# MainBoard.net
KiCad netlist of a schematic drawn in EAGLE
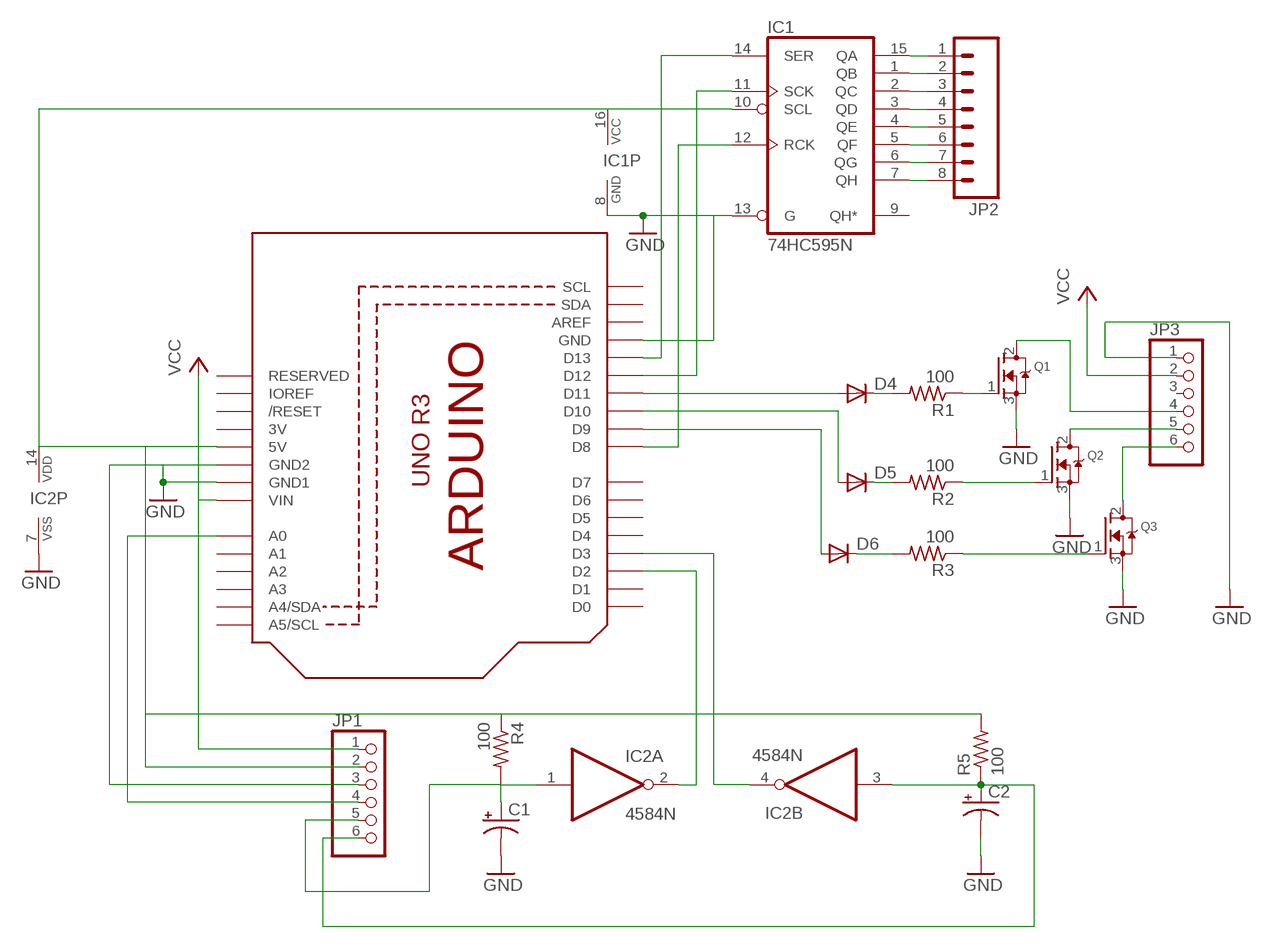
[diagram p0: schematic, sheet 1]

(export (version "E")
  (design (tool "Eeschema 10.0.6"))
  (components
    (comp (ref "C1")
      (value "CPOL-USE2.5-5")
      (footprint "eagle-import:E2,5-5")
      (libsource (lib "eagle-import") (part "CPOL-USE2.5-5"))
    )
    (comp (ref "C2")
      (value "CPOL-USE2.5-5")
      (footprint "eagle-import:E2,5-5")
      (libsource (lib "eagle-import") (part "CPOL-USE2.5-5"))
    )
    (comp (ref "D4")
      (value "1N4148DO35-7")
      (footprint "eagle-import:DO35-7")
      (libsource (lib "eagle-import") (part "1N4148DO35-7"))
    )
    (comp (ref "D5")
      (value "1N4148DO35-7")
      (footprint "eagle-import:DO35-7")
      (libsource (lib "eagle-import") (part "1N4148DO35-7"))
    )
    (comp (ref "D6")
      (value "1N4148DO35-7")
      (footprint "eagle-import:DO35-7")
      (libsource (lib "eagle-import") (part "1N4148DO35-7"))
    )
    (comp (ref "IC1")
      (value "74HC595N")
      (footprint "eagle-import:DIL16")
      (libsource (lib "eagle-import") (part "74595NHC"))
    )
    (comp (ref "IC2")
      (value "4584N")
      (footprint "eagle-import:DIL14")
      (libsource (lib "eagle-import") (part "4584N"))
    )
    (comp (ref "JP1")
      (value "PINHD-1X6LOCK")
      (footprint "eagle-import:1X06-BIGLOCK")
      (libsource (lib "eagle-import") (part "PINHD-1X6LOCK"))
    )
    (comp (ref "JP2")
      (value "M08LOCK")
      (footprint "eagle-import:1X08_LOCK")
      (libsource (lib "eagle-import") (part "M08LOCK"))
    )
    (comp (ref "JP3")
      (value "PINHD-1X6LOCK")
      (footprint "eagle-import:1X06-BIGLOCK")
      (libsource (lib "eagle-import") (part "PINHD-1X6LOCK"))
    )
    (comp (ref "Q1")
      (value "MOSFET-NGDS_TO220V")
      (footprint "eagle-import:TO220V")
      (libsource (lib "eagle-import") (part "MOSFET-NGDS_TO220V"))
    )
    (comp (ref "Q2")
      (value "MOSFET-NGDS_TO220V")
      (footprint "eagle-import:TO220V")
      (libsource (lib "eagle-import") (part "MOSFET-NGDS_TO220V"))
    )
    (comp (ref "Q3")
      (value "MOSFET-NGDS_TO220V")
      (footprint "eagle-import:TO220V")
      (libsource (lib "eagle-import") (part "MOSFET-NGDS_TO220V"))
    )
    (comp (ref "R1")
      (value "100")
      (footprint "eagle-import:0207_10")
      (libsource (lib "eagle-import") (part "R-US_0207/10"))
    )
    (comp (ref "R2")
      (value "100")
      (footprint "eagle-import:0207_10")
      (libsource (lib "eagle-import") (part "R-US_0207/10"))
    )
    (comp (ref "R3")
      (value "100")
      (footprint "eagle-import:0207_10")
      (libsource (lib "eagle-import") (part "R-US_0207/10"))
    )
    (comp (ref "R4")
      (value "100")
      (footprint "eagle-import:0207_10")
      (libsource (lib "eagle-import") (part "R-US_0207/10"))
    )
    (comp (ref "R5")
      (value "100")
      (footprint "eagle-import:0207_10")
      (libsource (lib "eagle-import") (part "R-US_0207/10"))
    )
    (comp (ref "U1")
      (value "ARDUINOR3-BPLACE")
      (footprint "eagle-import:ARDUINOR3-BPLACE")
      (libsource (lib "eagle-import") (part "ARDUINOR3-BPLACE"))
    )
  )
  (nets
    (net (code "1") (name "/3V") (class "Default")
      (node (ref "U1") (pin "3V") (pinfunction "3V_3V") (pintype "power_in"))
    )
    (net (code "2") (name "GND") (class "Default")
      (node (ref "C1") (pin "-") (pinfunction "-_-") (pintype "passive"))
      (node (ref "C2") (pin "-") (pinfunction "-_-") (pintype "passive"))
      (node (ref "IC1") (pin "13") (pinfunction "G_13") (pintype "input"))
      (node (ref "IC1") (pin "8") (pinfunction "GND_8") (pintype "power_in"))
      (node (ref "IC2") (pin "7") (pinfunction "VSS_7") (pintype "power_in"))
      (node (ref "JP1") (pin "3") (pinfunction "3_3") (pintype "passive"))
      (node (ref "JP3") (pin "1") (pinfunction "1_1") (pintype "passive"))
      (node (ref "Q1") (pin "3") (pinfunction "S_3") (pintype "bidirectional"))
      (node (ref "Q2") (pin "3") (pinfunction "S_3") (pintype "bidirectional"))
      (node (ref "Q3") (pin "3") (pinfunction "S_3") (pintype "bidirectional"))
      (node (ref "U1") (pin "GND") (pinfunction "GND_GND") (pintype "power_in"))
      (node (ref "U1") (pin "GND1") (pinfunction "GND1_GND1") (pintype "power_in"))
      (node (ref "U1") (pin "GND2") (pinfunction "GND2_GND2") (pintype "power_in"))
    )
    (net (code "3") (name "Net-(D4-PadA)") (class "Default")
      (node (ref "D4") (pin "A") (pinfunction "A_A") (pintype "passive"))
      (node (ref "U1") (pin "D11") (pinfunction "D11_D11") (pintype "bidirectional"))
    )
    (net (code "4") (name "Net-(D4-PadC)") (class "Default")
      (node (ref "D4") (pin "C") (pinfunction "C_C") (pintype "passive"))
      (node (ref "R1") (pin "2") (pinfunction "2_2") (pintype "passive"))
    )
    (net (code "5") (name "Net-(D5-PadA)") (class "Default")
      (node (ref "D5") (pin "A") (pinfunction "A_A") (pintype "passive"))
      (node (ref "U1") (pin "D10") (pinfunction "D10_D10") (pintype "bidirectional"))
    )
    (net (code "6") (name "Net-(D5-PadC)") (class "Default")
      (node (ref "D5") (pin "C") (pinfunction "C_C") (pintype "passive"))
      (node (ref "R2") (pin "2") (pinfunction "2_2") (pintype "passive"))
    )
    (net (code "7") (name "Net-(D6-PadA)") (class "Default")
      (node (ref "D6") (pin "A") (pinfunction "A_A") (pintype "passive"))
      (node (ref "U1") (pin "D9") (pinfunction "D9_D9") (pintype "bidirectional"))
    )
    (net (code "8") (name "Net-(D6-PadC)") (class "Default")
      (node (ref "D6") (pin "C") (pinfunction "C_C") (pintype "passive"))
      (node (ref "R3") (pin "2") (pinfunction "2_2") (pintype "passive"))
    )
    (net (code "9") (name "Net-(IC1A-QA)") (class "Default")
      (node (ref "IC1") (pin "15") (pinfunction "QA_15") (pintype "tri_state"))
      (node (ref "JP2") (pin "1") (pinfunction "1_1") (pintype "passive"))
    )
    (net (code "10") (name "Net-(IC1A-QB)") (class "Default")
      (node (ref "IC1") (pin "1") (pinfunction "QB_1") (pintype "tri_state"))
      (node (ref "JP2") (pin "2") (pinfunction "2_2") (pintype "passive"))
    )
    (net (code "11") (name "Net-(IC1A-QC)") (class "Default")
      (node (ref "IC1") (pin "2") (pinfunction "QC_2") (pintype "tri_state"))
      (node (ref "JP2") (pin "3") (pinfunction "3_3") (pintype "passive"))
    )
    (net (code "12") (name "Net-(IC1A-QD)") (class "Default")
      (node (ref "IC1") (pin "3") (pinfunction "QD_3") (pintype "tri_state"))
      (node (ref "JP2") (pin "4") (pinfunction "4_4") (pintype "passive"))
    )
    (net (code "13") (name "Net-(IC1A-QE)") (class "Default")
      (node (ref "IC1") (pin "4") (pinfunction "QE_4") (pintype "tri_state"))
      (node (ref "JP2") (pin "5") (pinfunction "5_5") (pintype "passive"))
    )
    (net (code "14") (name "Net-(IC1A-QF)") (class "Default")
      (node (ref "IC1") (pin "5") (pinfunction "QF_5") (pintype "tri_state"))
      (node (ref "JP2") (pin "6") (pinfunction "6_6") (pintype "passive"))
    )
    (net (code "15") (name "Net-(IC1A-QG)") (class "Default")
      (node (ref "IC1") (pin "6") (pinfunction "QG_6") (pintype "tri_state"))
      (node (ref "JP2") (pin "7") (pinfunction "7_7") (pintype "passive"))
    )
    (net (code "16") (name "Net-(IC1A-QH)") (class "Default")
      (node (ref "IC1") (pin "7") (pinfunction "QH_7") (pintype "tri_state"))
      (node (ref "JP2") (pin "8") (pinfunction "8_8") (pintype "passive"))
    )
    (net (code "17") (name "Net-(IC1A-RCK)") (class "Default")
      (node (ref "IC1") (pin "12") (pinfunction "RCK_12") (pintype "input"))
      (node (ref "U1") (pin "D8") (pinfunction "D8_D8") (pintype "bidirectional"))
    )
    (net (code "18") (name "Net-(IC1A-SCK)") (class "Default")
      (node (ref "IC1") (pin "11") (pinfunction "SCK_11") (pintype "input"))
      (node (ref "U1") (pin "D12") (pinfunction "D12_D12") (pintype "bidirectional"))
    )
    (net (code "19") (name "Net-(IC1A-SCL)") (class "Default")
      (node (ref "IC1") (pin "10") (pinfunction "SCL_10") (pintype "input"))
      (node (ref "IC1") (pin "16") (pinfunction "VCC_16") (pintype "power_in"))
      (node (ref "IC2") (pin "14") (pinfunction "VDD_14") (pintype "power_in"))
      (node (ref "JP1") (pin "2") (pinfunction "2_2") (pintype "passive"))
      (node (ref "R4") (pin "1") (pinfunction "1_1") (pintype "passive"))
      (node (ref "R5") (pin "2") (pinfunction "2_2") (pintype "passive"))
      (node (ref "U1") (pin "5V") (pinfunction "5V_5V") (pintype "power_in"))
    )
    (net (code "20") (name "Net-(IC1A-SER)") (class "Default")
      (node (ref "IC1") (pin "14") (pinfunction "SER_14") (pintype "input"))
      (node (ref "U1") (pin "D13") (pinfunction "D13_D13") (pintype "bidirectional"))
    )
    (net (code "21") (name "Net-(IC2A-I)") (class "Default")
      (node (ref "C1") (pin "+") (pinfunction "+_+") (pintype "passive"))
      (node (ref "IC2") (pin "1") (pinfunction "I_1") (pintype "input"))
      (node (ref "JP1") (pin "5") (pinfunction "5_5") (pintype "passive"))
      (node (ref "R4") (pin "2") (pinfunction "2_2") (pintype "passive"))
    )
    (net (code "22") (name "Net-(IC2A-O)") (class "Default")
      (node (ref "IC2") (pin "2") (pinfunction "O_2") (pintype "output"))
      (node (ref "U1") (pin "D2") (pinfunction "D2_D2") (pintype "bidirectional"))
    )
    (net (code "23") (name "Net-(IC2B-I)") (class "Default")
      (node (ref "C2") (pin "+") (pinfunction "+_+") (pintype "passive"))
      (node (ref "IC2") (pin "3") (pinfunction "I_3") (pintype "input"))
      (node (ref "JP1") (pin "6") (pinfunction "6_6") (pintype "passive"))
      (node (ref "R5") (pin "1") (pinfunction "1_1") (pintype "passive"))
    )
    (net (code "24") (name "Net-(IC2B-O)") (class "Default")
      (node (ref "IC2") (pin "4") (pinfunction "O_4") (pintype "output"))
      (node (ref "U1") (pin "D3") (pinfunction "D3_D3") (pintype "bidirectional"))
    )
    (net (code "25") (name "Net-(JP1-Pad4)") (class "Default")
      (node (ref "JP1") (pin "4") (pinfunction "4_4") (pintype "passive"))
      (node (ref "U1") (pin "A0") (pinfunction "A0_A0") (pintype "bidirectional"))
    )
    (net (code "26") (name "Net-(Q1-D)") (class "Default")
      (node (ref "JP3") (pin "4") (pinfunction "4_4") (pintype "passive"))
      (node (ref "Q1") (pin "2") (pinfunction "D_2") (pintype "bidirectional"))
    )
    (net (code "27") (name "Net-(Q1-G)") (class "Default")
      (node (ref "Q1") (pin "1") (pinfunction "G_1") (pintype "bidirectional"))
      (node (ref "R1") (pin "1") (pinfunction "1_1") (pintype "passive"))
    )
    (net (code "28") (name "Net-(Q2-D)") (class "Default")
      (node (ref "JP3") (pin "5") (pinfunction "5_5") (pintype "passive"))
      (node (ref "Q2") (pin "2") (pinfunction "D_2") (pintype "bidirectional"))
    )
    (net (code "29") (name "Net-(Q2-G)") (class "Default")
      (node (ref "Q2") (pin "1") (pinfunction "G_1") (pintype "bidirectional"))
      (node (ref "R2") (pin "1") (pinfunction "1_1") (pintype "passive"))
    )
    (net (code "30") (name "Net-(Q3-D)") (class "Default")
      (node (ref "JP3") (pin "6") (pinfunction "6_6") (pintype "passive"))
      (node (ref "Q3") (pin "2") (pinfunction "D_2") (pintype "bidirectional"))
    )
    (net (code "31") (name "Net-(Q3-G)") (class "Default")
      (node (ref "Q3") (pin "1") (pinfunction "G_1") (pintype "bidirectional"))
      (node (ref "R3") (pin "1") (pinfunction "1_1") (pintype "passive"))
    )
    (net (code "32") (name "VCC") (class "Default")
      (node (ref "JP1") (pin "1") (pinfunction "1_1") (pintype "passive"))
      (node (ref "JP3") (pin "2") (pinfunction "2_2") (pintype "passive"))
      (node (ref "U1") (pin "VIN") (pinfunction "VIN_VIN") (pintype "power_in"))
    )
    (net (code "33") (name "unconnected-(IC1A-QH*-Pad9)") (class "Default")
      (node (ref "IC1") (pin "9") (pinfunction "QH*_9") (pintype "tri_state"))
    )
    (net (code "34") (name "unconnected-(JP3-Pad3)") (class "Default")
      (node (ref "JP3") (pin "3") (pinfunction "3_3") (pintype "passive"))
    )
    (net (code "35") (name "unconnected-(U1-A4{slash}SDA-PadA4)") (class "Default")
      (node (ref "U1") (pin "A4") (pinfunction "A4/SDA_A4") (pintype "bidirectional"))
    )
    (net (code "36") (name "unconnected-(U1-A5{slash}SCL-PadA5)") (class "Default")
      (node (ref "U1") (pin "A5") (pinfunction "A5/SCL_A5") (pintype "bidirectional"))
    )
    (net (code "37") (name "unconnected-(U1-PadA1)") (class "Default")
      (node (ref "U1") (pin "A1") (pinfunction "A1_A1") (pintype "bidirectional"))
    )
    (net (code "38") (name "unconnected-(U1-PadA2)") (class "Default")
      (node (ref "U1") (pin "A2") (pinfunction "A2_A2") (pintype "bidirectional"))
    )
    (net (code "39") (name "unconnected-(U1-PadA3)") (class "Default")
      (node (ref "U1") (pin "A3") (pinfunction "A3_A3") (pintype "bidirectional"))
    )
    (net (code "40") (name "unconnected-(U1-PadAREF)") (class "Default")
      (node (ref "U1") (pin "AREF") (pinfunction "AREF_AREF") (pintype "bidirectional"))
    )
    (net (code "41") (name "unconnected-(U1-PadD0)") (class "Default")
      (node (ref "U1") (pin "D0") (pinfunction "D0_D0") (pintype "bidirectional"))
    )
    (net (code "42") (name "unconnected-(U1-PadD1)") (class "Default")
      (node (ref "U1") (pin "D1") (pinfunction "D1_D1") (pintype "bidirectional"))
    )
    (net (code "43") (name "unconnected-(U1-PadD4)") (class "Default")
      (node (ref "U1") (pin "D4") (pinfunction "D4_D4") (pintype "bidirectional"))
    )
    (net (code "44") (name "unconnected-(U1-PadD5)") (class "Default")
      (node (ref "U1") (pin "D5") (pinfunction "D5_D5") (pintype "bidirectional"))
    )
    (net (code "45") (name "unconnected-(U1-PadD6)") (class "Default")
      (node (ref "U1") (pin "D6") (pinfunction "D6_D6") (pintype "bidirectional"))
    )
    (net (code "46") (name "unconnected-(U1-PadD7)") (class "Default")
      (node (ref "U1") (pin "D7") (pinfunction "D7_D7") (pintype "bidirectional"))
    )
    (net (code "47") (name "unconnected-(U1-PadIOREF)") (class "Default")
      (node (ref "U1") (pin "IOREF") (pinfunction "IOREF_IOREF") (pintype "output"))
    )
    (net (code "48") (name "unconnected-(U1-PadRESERVED)") (class "Default")
      (node (ref "U1") (pin "RESERVED") (pinfunction "RESERVED_RESERVED") (pintype "no_connect"))
    )
    (net (code "49") (name "unconnected-(U1-PadSCL)") (class "Default")
      (node (ref "U1") (pin "SCL") (pinfunction "SCL_SCL") (pintype "bidirectional"))
    )
    (net (code "50") (name "unconnected-(U1-PadSDA)") (class "Default")
      (node (ref "U1") (pin "SDA") (pinfunction "SDA_SDA") (pintype "bidirectional"))
    )
    (net (code "51") (name "unconnected-(U1-{slash}RESET-PadRESET)") (class "Default")
      (node (ref "U1") (pin "RESET") (pinfunction "/RESET_RESET") (pintype "bidirectional"))
    )
  )
)
